# FOTA_MicroController_Power_Switch.net
KiCad netlist of a schematic drawn in Altium Designer
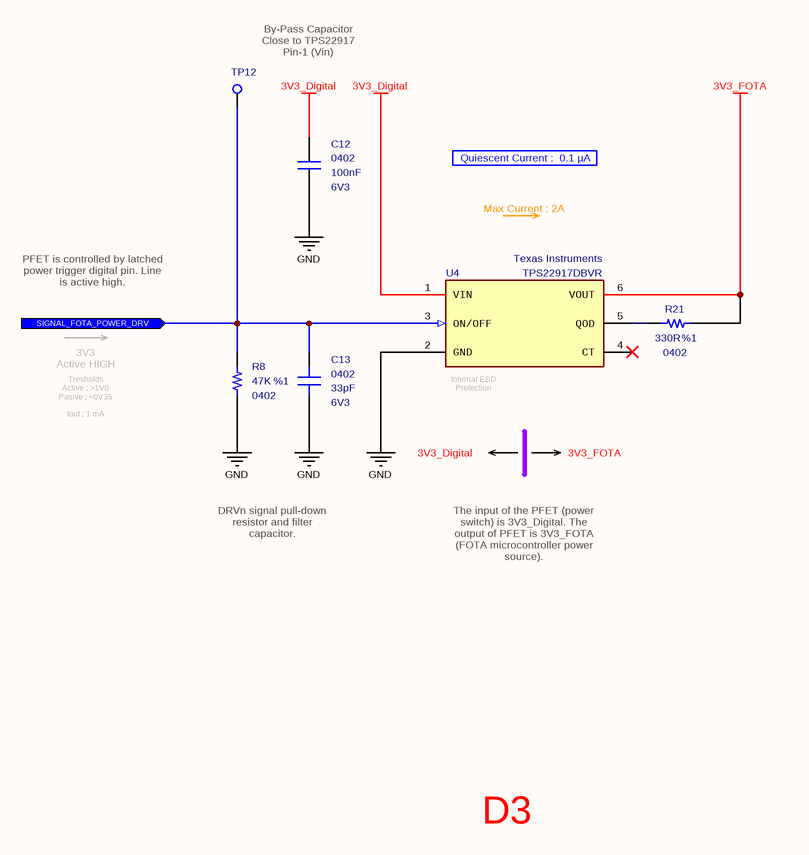
[diagram p0: FOTA MicroController Power Switch.SchDoc]

(export (version "E")
  (design (tool "Eeschema 10.0.6"))
  (components
    (comp (ref "C12")
      (value "100nF")
      (footprint "CAPACITOR_0402")
      (description "Capacitor - 100nF [0402-6V3] (Ceramic)")
      (fields
        (field (name "MANUFACTURER_PART_NUMBER") "04026D104KAT4A")
        (field (name "MOUSER_PART_NUMBER") "581-04026D104KAT4A")
        (field (name "CASE") "0402")
        (field (name "VOLTAGE") "6V3")
      )
      (libsource (lib "Ovoo_Schematic") (part "Capacitor - 100nF [0402-6V3]"))
    )
    (comp (ref "C13")
      (value "33pF")
      (footprint "CAPACITOR_0402")
      (description "Capacitor - 33pF [0402] (Ceramic)")
      (fields
        (field (name "MANUFACTURER_PART_NUMBER") "C0402C330J9RACAUTO")
        (field (name "MOUSER_PART_NUMBER") "80-C0402C330J9RAUTO")
        (field (name "CASE") "0402")
        (field (name "VOLTAGE") "6V3")
      )
      (libsource (lib "Ovoo_Schematic") (part "Capacitor - 33pF [0402-6V3]"))
    )
    (comp (ref "R8")
      (value "47K")
      (footprint "RESISTOR_0402")
      (description "Thick Film Resistors - SMD 1/16 W 47 Kohms 1%")
      (fields
        (field (name "MANUFACTURER_PART_NUMBER") "CRCW040247K0FKED")
        (field (name "MOUSER_PART_NUMBER") "71-CRCW0402-47K-E3")
        (field (name "TOLERANCE") "%1")
        (field (name "CASE") "0402")
      )
      (libsource (lib "Ovoo_Schematic") (part "Resistor - 47K"))
    )
    (comp (ref "R21")
      (value "330R")
      (footprint "RESISTOR_0402")
      (description "Thick Film Resistors - SMD 1/16 W 330 Ohm 1%")
      (fields
        (field (name "MANUFACTURER_PART_NUMBER") "CRCW0402330RFKED")
        (field (name "MOUSER_PART_NUMBER") "71-CRCW0402-330-E3")
        (field (name "TOLERANCE") "%1")
        (field (name "CASE") "0402")
      )
      (libsource (lib "Ovoo_Schematic") (part "Resistor - 330R"))
    )
    (comp (ref "TP12")
      (value "PCB - Test Point")
      (footprint "Test_Pad - Hole")
      (description "Test Point")
      (libsource (lib "Ovoo_Schematic") (part "PCB - Test Point"))
    )
    (comp (ref "U4")
      (value "Power Switch")
      (footprint "SOT-23-6")
      (description "Power Switch MosFet")
      (fields
        (field (name "MOUSER_PART_NUMBER") "595-TPS22917DBVR")
        (field (name "MANUFACTURER_PART_NUMBER") "TPS22917DBVR")
        (field (name "MANUFACTURER_NAME") "Texas Instruments")
      )
      (libsource (lib "Ovoo_Schematic") (part "IC - TPS22917DBVR"))
    )
  )
  (nets
    (net (code "1") (name "/SIGNAL_FOTA_POWER_DRV") (class "Default")
      (node (ref "C13") (pin "2") (pinfunction "2_2") (pintype "passive"))
      (node (ref "R8") (pin "2") (pinfunction "2_2") (pintype "passive"))
      (node (ref "TP12") (pin "1") (pinfunction "1_1") (pintype "passive"))
      (node (ref "U4") (pin "3") (pinfunction "ON/OFF_3") (pintype "input"))
    )
    (net (code "2") (name "3V3_Digital") (class "Default")
      (node (ref "C12") (pin "1") (pinfunction "1_1") (pintype "passive"))
      (node (ref "U4") (pin "1") (pinfunction "VIN_1") (pintype "power_in"))
    )
    (net (code "3") (name "3V3_FOTA") (class "Default")
      (node (ref "R21") (pin "1") (pinfunction "1_1") (pintype "passive"))
      (node (ref "U4") (pin "6") (pinfunction "VOUT_6") (pintype "power_in"))
    )
    (net (code "4") (name "GND") (class "Default")
      (node (ref "C12") (pin "2") (pinfunction "2_2") (pintype "passive"))
      (node (ref "C13") (pin "1") (pinfunction "1_1") (pintype "passive"))
      (node (ref "R8") (pin "1") (pinfunction "1_1") (pintype "passive"))
      (node (ref "U4") (pin "2") (pinfunction "GND_2") (pintype "power_in"))
    )
    (net (code "5") (name "Net-(U4-QOD)") (class "Default")
      (node (ref "R21") (pin "2") (pinfunction "2_2") (pintype "passive"))
      (node (ref "U4") (pin "5") (pinfunction "QOD_5") (pintype "power_in"))
    )
    (net (code "6") (name "unconnected-(U4-CT-Pad4)") (class "Default")
      (node (ref "U4") (pin "4") (pinfunction "CT_4") (pintype "power_in+no_connect"))
    )
  )
)
